# Placa.net
KiCad netlist of a schematic drawn in EAGLE
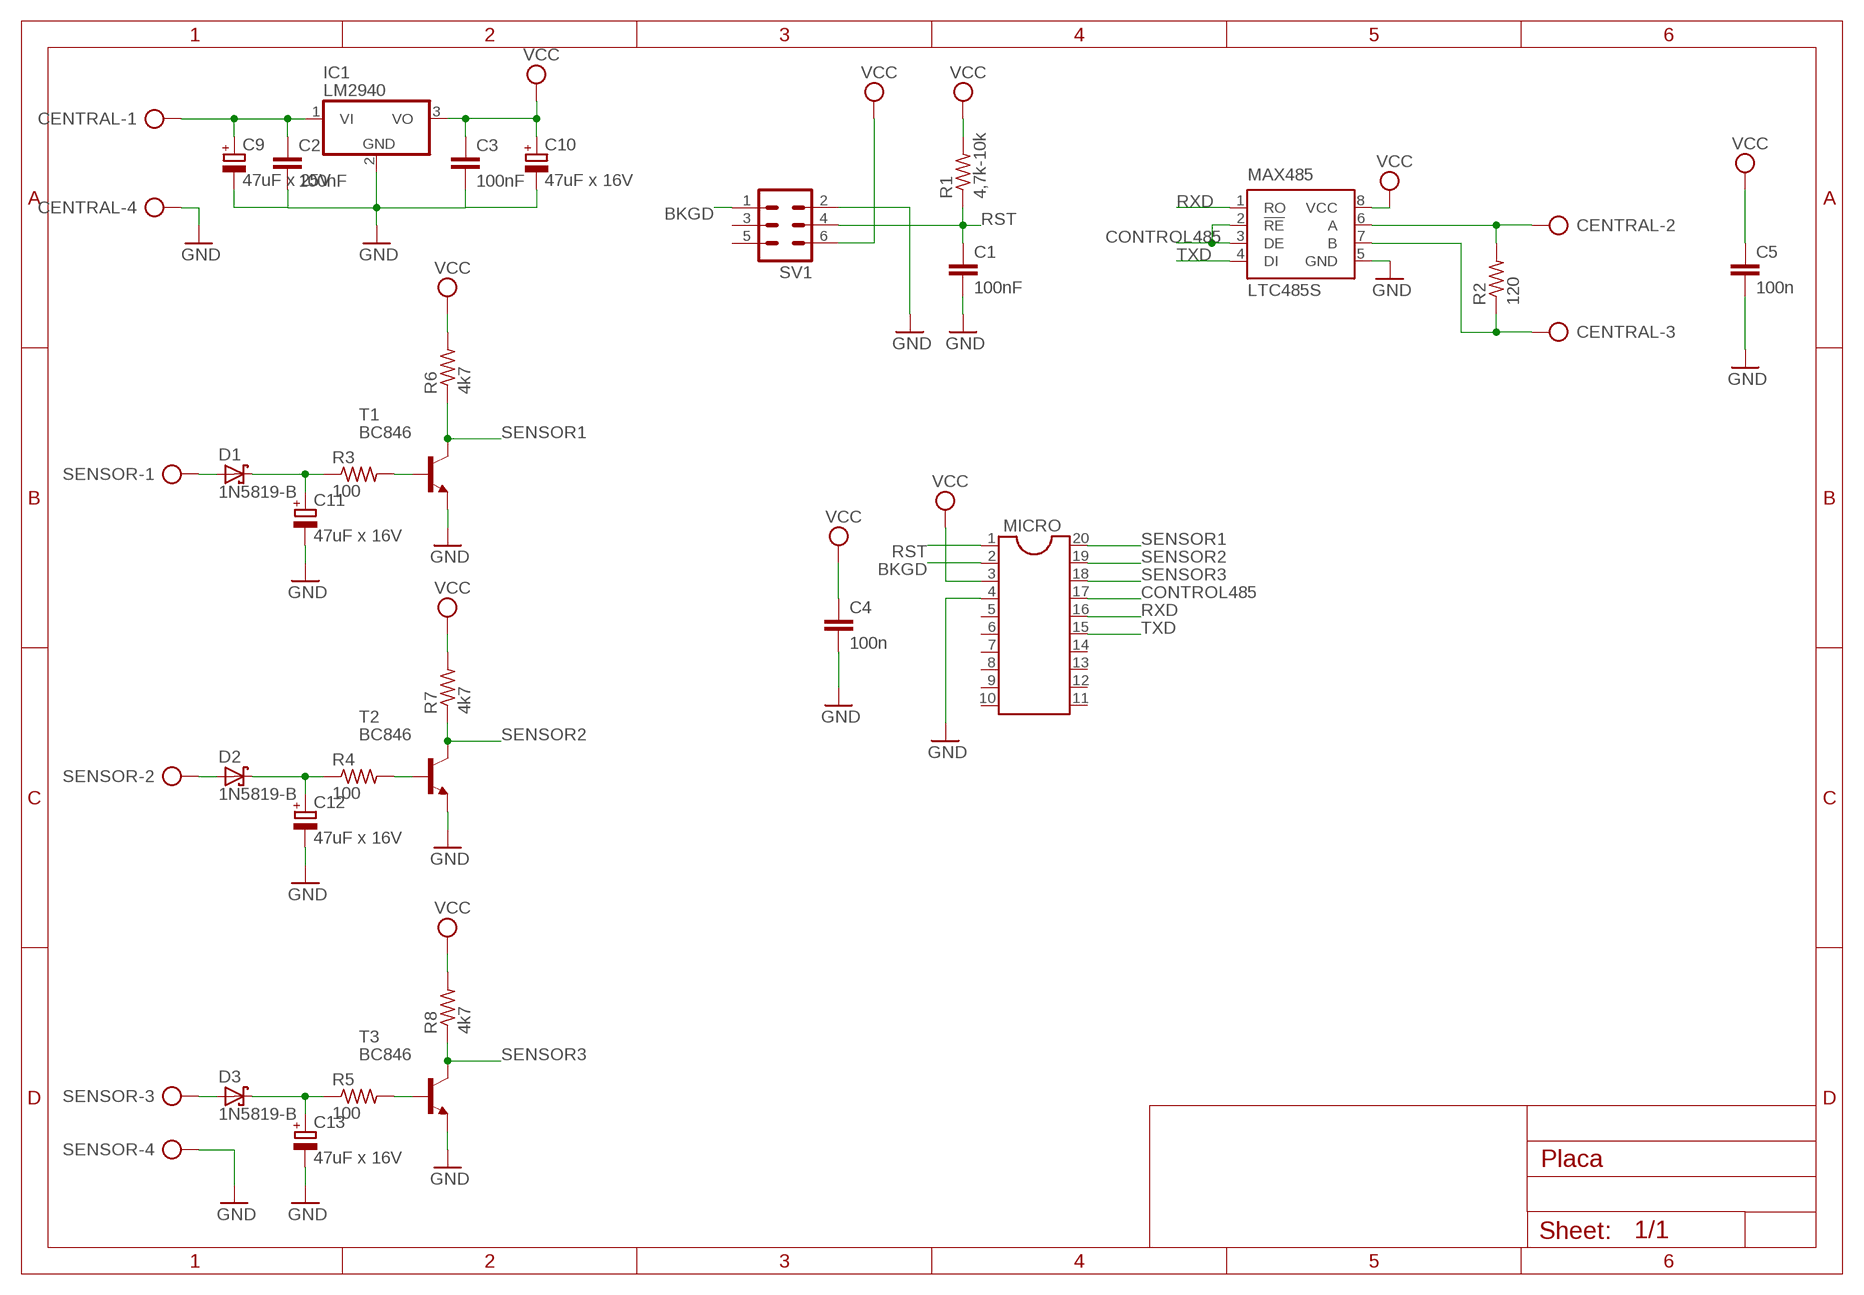
[diagram p0: schematic, sheet 1]

(export (version "E")
  (design (tool "Eeschema 10.0.6"))
  (components
    (comp (ref "C1")
      (value "100nF")
      (footprint "eagle-import:C0805")
      (libsource (lib "eagle-import") (part "C-EUC0805"))
    )
    (comp (ref "C2")
      (value "100nF")
      (footprint "eagle-import:C0805")
      (libsource (lib "eagle-import") (part "C-EUC0805"))
    )
    (comp (ref "C3")
      (value "100nF")
      (footprint "eagle-import:C0805")
      (libsource (lib "eagle-import") (part "C-EUC0805"))
    )
    (comp (ref "C4")
      (value "100n")
      (footprint "eagle-import:C0805")
      (libsource (lib "eagle-import") (part "C-EUC0805"))
    )
    (comp (ref "C5")
      (value "100n")
      (footprint "eagle-import:C0805")
      (libsource (lib "eagle-import") (part "C-EUC0805"))
    )
    (comp (ref "C9")
      (value "47uF x 25V")
      (footprint "eagle-import:E2,5-6E")
      (libsource (lib "eagle-import") (part "CPOL-EUE2,5-6E"))
    )
    (comp (ref "C10")
      (value "47uF x 16V")
      (footprint "eagle-import:E2,5-6E")
      (libsource (lib "eagle-import") (part "CPOL-EUE2,5-6E"))
    )
    (comp (ref "C11")
      (value "47uF x 16V")
      (footprint "eagle-import:E2,5-6E")
      (libsource (lib "eagle-import") (part "CPOL-EUE2,5-6E"))
    )
    (comp (ref "C12")
      (value "47uF x 16V")
      (footprint "eagle-import:E2,5-6E")
      (libsource (lib "eagle-import") (part "CPOL-EUE2,5-6E"))
    )
    (comp (ref "C13")
      (value "47uF x 16V")
      (footprint "eagle-import:E2,5-6E")
      (libsource (lib "eagle-import") (part "CPOL-EUE2,5-6E"))
    )
    (comp (ref "CENTRAL")
      (value "AK300/4")
      (footprint "eagle-import:AK300_4")
      (libsource (lib "eagle-import") (part "AK300/4"))
    )
    (comp (ref "D1")
      (value "1N5819-B")
      (footprint "eagle-import:DO41-7.6")
      (libsource (lib "eagle-import") (part "1N5819-B"))
    )
    (comp (ref "D2")
      (value "1N5819-B")
      (footprint "eagle-import:DO41-7.6")
      (libsource (lib "eagle-import") (part "1N5819-B"))
    )
    (comp (ref "D3")
      (value "1N5819-B")
      (footprint "eagle-import:DO41-7.6")
      (libsource (lib "eagle-import") (part "1N5819-B"))
    )
    (comp (ref "IC1")
      (value "LM2940")
      (footprint "eagle-import:TO220V")
      (libsource (lib "eagle-import") (part "78TV05"))
    )
    (comp (ref "MAX485")
      (value "LTC485S")
      (footprint "eagle-import:SOIC8")
      (libsource (lib "eagle-import") (part "LTC485S"))
    )
    (comp (ref "MICRO")
      (value "DIL20")
      (footprint "eagle-import:DIL20")
      (libsource (lib "eagle-import") (part "DIL20"))
    )
    (comp (ref "R1")
      (value "4,7k-10k")
      (footprint "eagle-import:R0805")
      (libsource (lib "eagle-import") (part "R-US_R0805"))
    )
    (comp (ref "R2")
      (value "120")
      (footprint "eagle-import:R0805")
      (libsource (lib "eagle-import") (part "R-US_R0805"))
    )
    (comp (ref "R3")
      (value "100")
      (footprint "eagle-import:R0805")
      (libsource (lib "eagle-import") (part "R-US_R0805"))
    )
    (comp (ref "R4")
      (value "100")
      (footprint "eagle-import:R0805")
      (libsource (lib "eagle-import") (part "R-US_R0805"))
    )
    (comp (ref "R5")
      (value "100")
      (footprint "eagle-import:R0805")
      (libsource (lib "eagle-import") (part "R-US_R0805"))
    )
    (comp (ref "R6")
      (value "4k7")
      (footprint "eagle-import:R0805")
      (libsource (lib "eagle-import") (part "R-US_R0805"))
    )
    (comp (ref "R7")
      (value "4k7")
      (footprint "eagle-import:R0805")
      (libsource (lib "eagle-import") (part "R-US_R0805"))
    )
    (comp (ref "R8")
      (value "4k7")
      (footprint "eagle-import:R0805")
      (libsource (lib "eagle-import") (part "R-US_R0805"))
    )
    (comp (ref "SENSOR")
      (value "AK300/4")
      (footprint "eagle-import:AK300_4")
      (libsource (lib "eagle-import") (part "AK300/4"))
    )
    (comp (ref "SV1")
      (value "MA03-2")
      (footprint "eagle-import:MA03-2")
      (libsource (lib "eagle-import") (part "MA03-2"))
    )
    (comp (ref "T1")
      (value "BC846")
      (footprint "eagle-import:SOT23")
      (libsource (lib "eagle-import") (part "BC846"))
    )
    (comp (ref "T2")
      (value "BC846")
      (footprint "eagle-import:SOT23")
      (libsource (lib "eagle-import") (part "BC846"))
    )
    (comp (ref "T3")
      (value "BC846")
      (footprint "eagle-import:SOT23")
      (libsource (lib "eagle-import") (part "BC846"))
    )
  )
  (nets
    (net (code "1") (name "/BKGD") (class "Default")
      (node (ref "MICRO") (pin "2") (pinfunction "2_2") (pintype "passive"))
      (node (ref "SV1") (pin "1") (pinfunction "1_1") (pintype "passive"))
    )
    (net (code "2") (name "/CONTROL485") (class "Default")
      (node (ref "MAX485") (pin "2") (pinfunction "~{RE}_2") (pintype "input"))
      (node (ref "MAX485") (pin "3") (pinfunction "DE_3") (pintype "input"))
      (node (ref "MICRO") (pin "17") (pinfunction "17_17") (pintype "passive"))
    )
    (net (code "3") (name "/RST") (class "Default")
      (node (ref "C1") (pin "1") (pinfunction "1_1") (pintype "passive"))
      (node (ref "MICRO") (pin "1") (pinfunction "1_1") (pintype "passive"))
      (node (ref "R1") (pin "1") (pinfunction "1_1") (pintype "passive"))
      (node (ref "SV1") (pin "4") (pinfunction "4_4") (pintype "passive"))
    )
    (net (code "4") (name "/RXD") (class "Default")
      (node (ref "MAX485") (pin "1") (pinfunction "RO_1") (pintype "output"))
      (node (ref "MICRO") (pin "16") (pinfunction "16_16") (pintype "passive"))
    )
    (net (code "5") (name "/SENSOR1") (class "Default")
      (node (ref "MICRO") (pin "20") (pinfunction "20_20") (pintype "passive"))
      (node (ref "R6") (pin "1") (pinfunction "1_1") (pintype "passive"))
      (node (ref "T1") (pin "3") (pinfunction "C_3") (pintype "passive"))
    )
    (net (code "6") (name "/SENSOR2") (class "Default")
      (node (ref "MICRO") (pin "19") (pinfunction "19_19") (pintype "passive"))
      (node (ref "R7") (pin "1") (pinfunction "1_1") (pintype "passive"))
      (node (ref "T2") (pin "3") (pinfunction "C_3") (pintype "passive"))
    )
    (net (code "7") (name "/SENSOR3") (class "Default")
      (node (ref "MICRO") (pin "18") (pinfunction "18_18") (pintype "passive"))
      (node (ref "R8") (pin "1") (pinfunction "1_1") (pintype "passive"))
      (node (ref "T3") (pin "3") (pinfunction "C_3") (pintype "passive"))
    )
    (net (code "8") (name "/TXD") (class "Default")
      (node (ref "MAX485") (pin "4") (pinfunction "DI_4") (pintype "input"))
      (node (ref "MICRO") (pin "15") (pinfunction "15_15") (pintype "passive"))
    )
    (net (code "9") (name "GND") (class "Default")
      (node (ref "C1") (pin "2") (pinfunction "2_2") (pintype "passive"))
      (node (ref "C10") (pin "-") (pinfunction "-_-") (pintype "passive"))
      (node (ref "C11") (pin "-") (pinfunction "-_-") (pintype "passive"))
      (node (ref "C12") (pin "-") (pinfunction "-_-") (pintype "passive"))
      (node (ref "C13") (pin "-") (pinfunction "-_-") (pintype "passive"))
      (node (ref "C2") (pin "2") (pinfunction "2_2") (pintype "passive"))
      (node (ref "C3") (pin "2") (pinfunction "2_2") (pintype "passive"))
      (node (ref "C4") (pin "2") (pinfunction "2_2") (pintype "passive"))
      (node (ref "C5") (pin "2") (pinfunction "2_2") (pintype "passive"))
      (node (ref "C9") (pin "-") (pinfunction "-_-") (pintype "passive"))
      (node (ref "CENTRAL") (pin "4") (pinfunction "KL_4") (pintype "passive"))
      (node (ref "IC1") (pin "2") (pinfunction "GND_2") (pintype "passive"))
      (node (ref "MAX485") (pin "5") (pinfunction "GND_5") (pintype "input"))
      (node (ref "MICRO") (pin "4") (pinfunction "4_4") (pintype "passive"))
      (node (ref "SENSOR") (pin "4") (pinfunction "KL_4") (pintype "passive"))
      (node (ref "SV1") (pin "2") (pinfunction "2_2") (pintype "passive"))
      (node (ref "T1") (pin "2") (pinfunction "E_2") (pintype "passive"))
      (node (ref "T2") (pin "2") (pinfunction "E_2") (pintype "passive"))
      (node (ref "T3") (pin "2") (pinfunction "E_2") (pintype "passive"))
    )
    (net (code "10") (name "Net-(C11-Pad+)") (class "Default")
      (node (ref "C11") (pin "+") (pinfunction "+_+") (pintype "passive"))
      (node (ref "D1") (pin "C") (pinfunction "C_C") (pintype "passive"))
      (node (ref "R3") (pin "1") (pinfunction "1_1") (pintype "passive"))
    )
    (net (code "11") (name "Net-(C12-Pad+)") (class "Default")
      (node (ref "C12") (pin "+") (pinfunction "+_+") (pintype "passive"))
      (node (ref "D2") (pin "C") (pinfunction "C_C") (pintype "passive"))
      (node (ref "R4") (pin "1") (pinfunction "1_1") (pintype "passive"))
    )
    (net (code "12") (name "Net-(C13-Pad+)") (class "Default")
      (node (ref "C13") (pin "+") (pinfunction "+_+") (pintype "passive"))
      (node (ref "D3") (pin "C") (pinfunction "C_C") (pintype "passive"))
      (node (ref "R5") (pin "1") (pinfunction "1_1") (pintype "passive"))
    )
    (net (code "13") (name "Net-(CENTRALA-KL)") (class "Default")
      (node (ref "C2") (pin "1") (pinfunction "1_1") (pintype "passive"))
      (node (ref "C9") (pin "+") (pinfunction "+_+") (pintype "passive"))
      (node (ref "CENTRAL") (pin "1") (pinfunction "KL_1") (pintype "passive"))
      (node (ref "IC1") (pin "1") (pinfunction "VI_1") (pintype "input"))
    )
    (net (code "14") (name "Net-(CENTRALB-KL)") (class "Default")
      (node (ref "CENTRAL") (pin "2") (pinfunction "KL_2") (pintype "passive"))
      (node (ref "MAX485") (pin "6") (pinfunction "A_6") (pintype "bidirectional"))
      (node (ref "R2") (pin "2") (pinfunction "2_2") (pintype "passive"))
    )
    (net (code "15") (name "Net-(CENTRALC-KL)") (class "Default")
      (node (ref "CENTRAL") (pin "3") (pinfunction "KL_3") (pintype "passive"))
      (node (ref "MAX485") (pin "7") (pinfunction "B_7") (pintype "bidirectional"))
      (node (ref "R2") (pin "1") (pinfunction "1_1") (pintype "passive"))
    )
    (net (code "16") (name "Net-(SENSORA-KL)") (class "Default")
      (node (ref "D1") (pin "A") (pinfunction "A_A") (pintype "passive"))
      (node (ref "SENSOR") (pin "1") (pinfunction "KL_1") (pintype "passive"))
    )
    (net (code "17") (name "Net-(SENSORB-KL)") (class "Default")
      (node (ref "D2") (pin "A") (pinfunction "A_A") (pintype "passive"))
      (node (ref "SENSOR") (pin "2") (pinfunction "KL_2") (pintype "passive"))
    )
    (net (code "18") (name "Net-(SENSORC-KL)") (class "Default")
      (node (ref "D3") (pin "A") (pinfunction "A_A") (pintype "passive"))
      (node (ref "SENSOR") (pin "3") (pinfunction "KL_3") (pintype "passive"))
    )
    (net (code "19") (name "Net-(T1-B)") (class "Default")
      (node (ref "R3") (pin "2") (pinfunction "2_2") (pintype "passive"))
      (node (ref "T1") (pin "1") (pinfunction "B_1") (pintype "passive"))
    )
    (net (code "20") (name "Net-(T2-B)") (class "Default")
      (node (ref "R4") (pin "2") (pinfunction "2_2") (pintype "passive"))
      (node (ref "T2") (pin "1") (pinfunction "B_1") (pintype "passive"))
    )
    (net (code "21") (name "Net-(T3-B)") (class "Default")
      (node (ref "R5") (pin "2") (pinfunction "2_2") (pintype "passive"))
      (node (ref "T3") (pin "1") (pinfunction "B_1") (pintype "passive"))
    )
    (net (code "22") (name "VCC") (class "Default")
      (node (ref "C10") (pin "+") (pinfunction "+_+") (pintype "passive"))
      (node (ref "C3") (pin "1") (pinfunction "1_1") (pintype "passive"))
      (node (ref "C4") (pin "1") (pinfunction "1_1") (pintype "passive"))
      (node (ref "C5") (pin "1") (pinfunction "1_1") (pintype "passive"))
      (node (ref "IC1") (pin "3") (pinfunction "VO_3") (pintype "passive"))
      (node (ref "MAX485") (pin "8") (pinfunction "VCC_8") (pintype "input"))
      (node (ref "MICRO") (pin "3") (pinfunction "3_3") (pintype "passive"))
      (node (ref "R1") (pin "2") (pinfunction "2_2") (pintype "passive"))
      (node (ref "R6") (pin "2") (pinfunction "2_2") (pintype "passive"))
      (node (ref "R7") (pin "2") (pinfunction "2_2") (pintype "passive"))
      (node (ref "R8") (pin "2") (pinfunction "2_2") (pintype "passive"))
      (node (ref "SV1") (pin "6") (pinfunction "6_6") (pintype "passive"))
    )
    (net (code "23") (name "unconnected-(MICRO-Pad5)") (class "Default")
      (node (ref "MICRO") (pin "5") (pinfunction "5_5") (pintype "passive"))
    )
    (net (code "24") (name "unconnected-(MICRO-Pad6)") (class "Default")
      (node (ref "MICRO") (pin "6") (pinfunction "6_6") (pintype "passive"))
    )
    (net (code "25") (name "unconnected-(MICRO-Pad7)") (class "Default")
      (node (ref "MICRO") (pin "7") (pinfunction "7_7") (pintype "passive"))
    )
    (net (code "26") (name "unconnected-(MICRO-Pad8)") (class "Default")
      (node (ref "MICRO") (pin "8") (pinfunction "8_8") (pintype "passive"))
    )
    (net (code "27") (name "unconnected-(MICRO-Pad9)") (class "Default")
      (node (ref "MICRO") (pin "9") (pinfunction "9_9") (pintype "passive"))
    )
    (net (code "28") (name "unconnected-(MICRO-Pad10)") (class "Default")
      (node (ref "MICRO") (pin "10") (pinfunction "10_10") (pintype "passive"))
    )
    (net (code "29") (name "unconnected-(MICRO-Pad11)") (class "Default")
      (node (ref "MICRO") (pin "11") (pinfunction "11_11") (pintype "passive"))
    )
    (net (code "30") (name "unconnected-(MICRO-Pad12)") (class "Default")
      (node (ref "MICRO") (pin "12") (pinfunction "12_12") (pintype "passive"))
    )
    (net (code "31") (name "unconnected-(MICRO-Pad13)") (class "Default")
      (node (ref "MICRO") (pin "13") (pinfunction "13_13") (pintype "passive"))
    )
    (net (code "32") (name "unconnected-(MICRO-Pad14)") (class "Default")
      (node (ref "MICRO") (pin "14") (pinfunction "14_14") (pintype "passive"))
    )
    (net (code "33") (name "unconnected-(SV1-Pad3)") (class "Default")
      (node (ref "SV1") (pin "3") (pinfunction "3_3") (pintype "passive"))
    )
    (net (code "34") (name "unconnected-(SV1-Pad5)") (class "Default")
      (node (ref "SV1") (pin "5") (pinfunction "5_5") (pintype "passive"))
    )
  )
)
